# PFC_Stage.net
KiCad netlist of a schematic drawn in Altium Designer
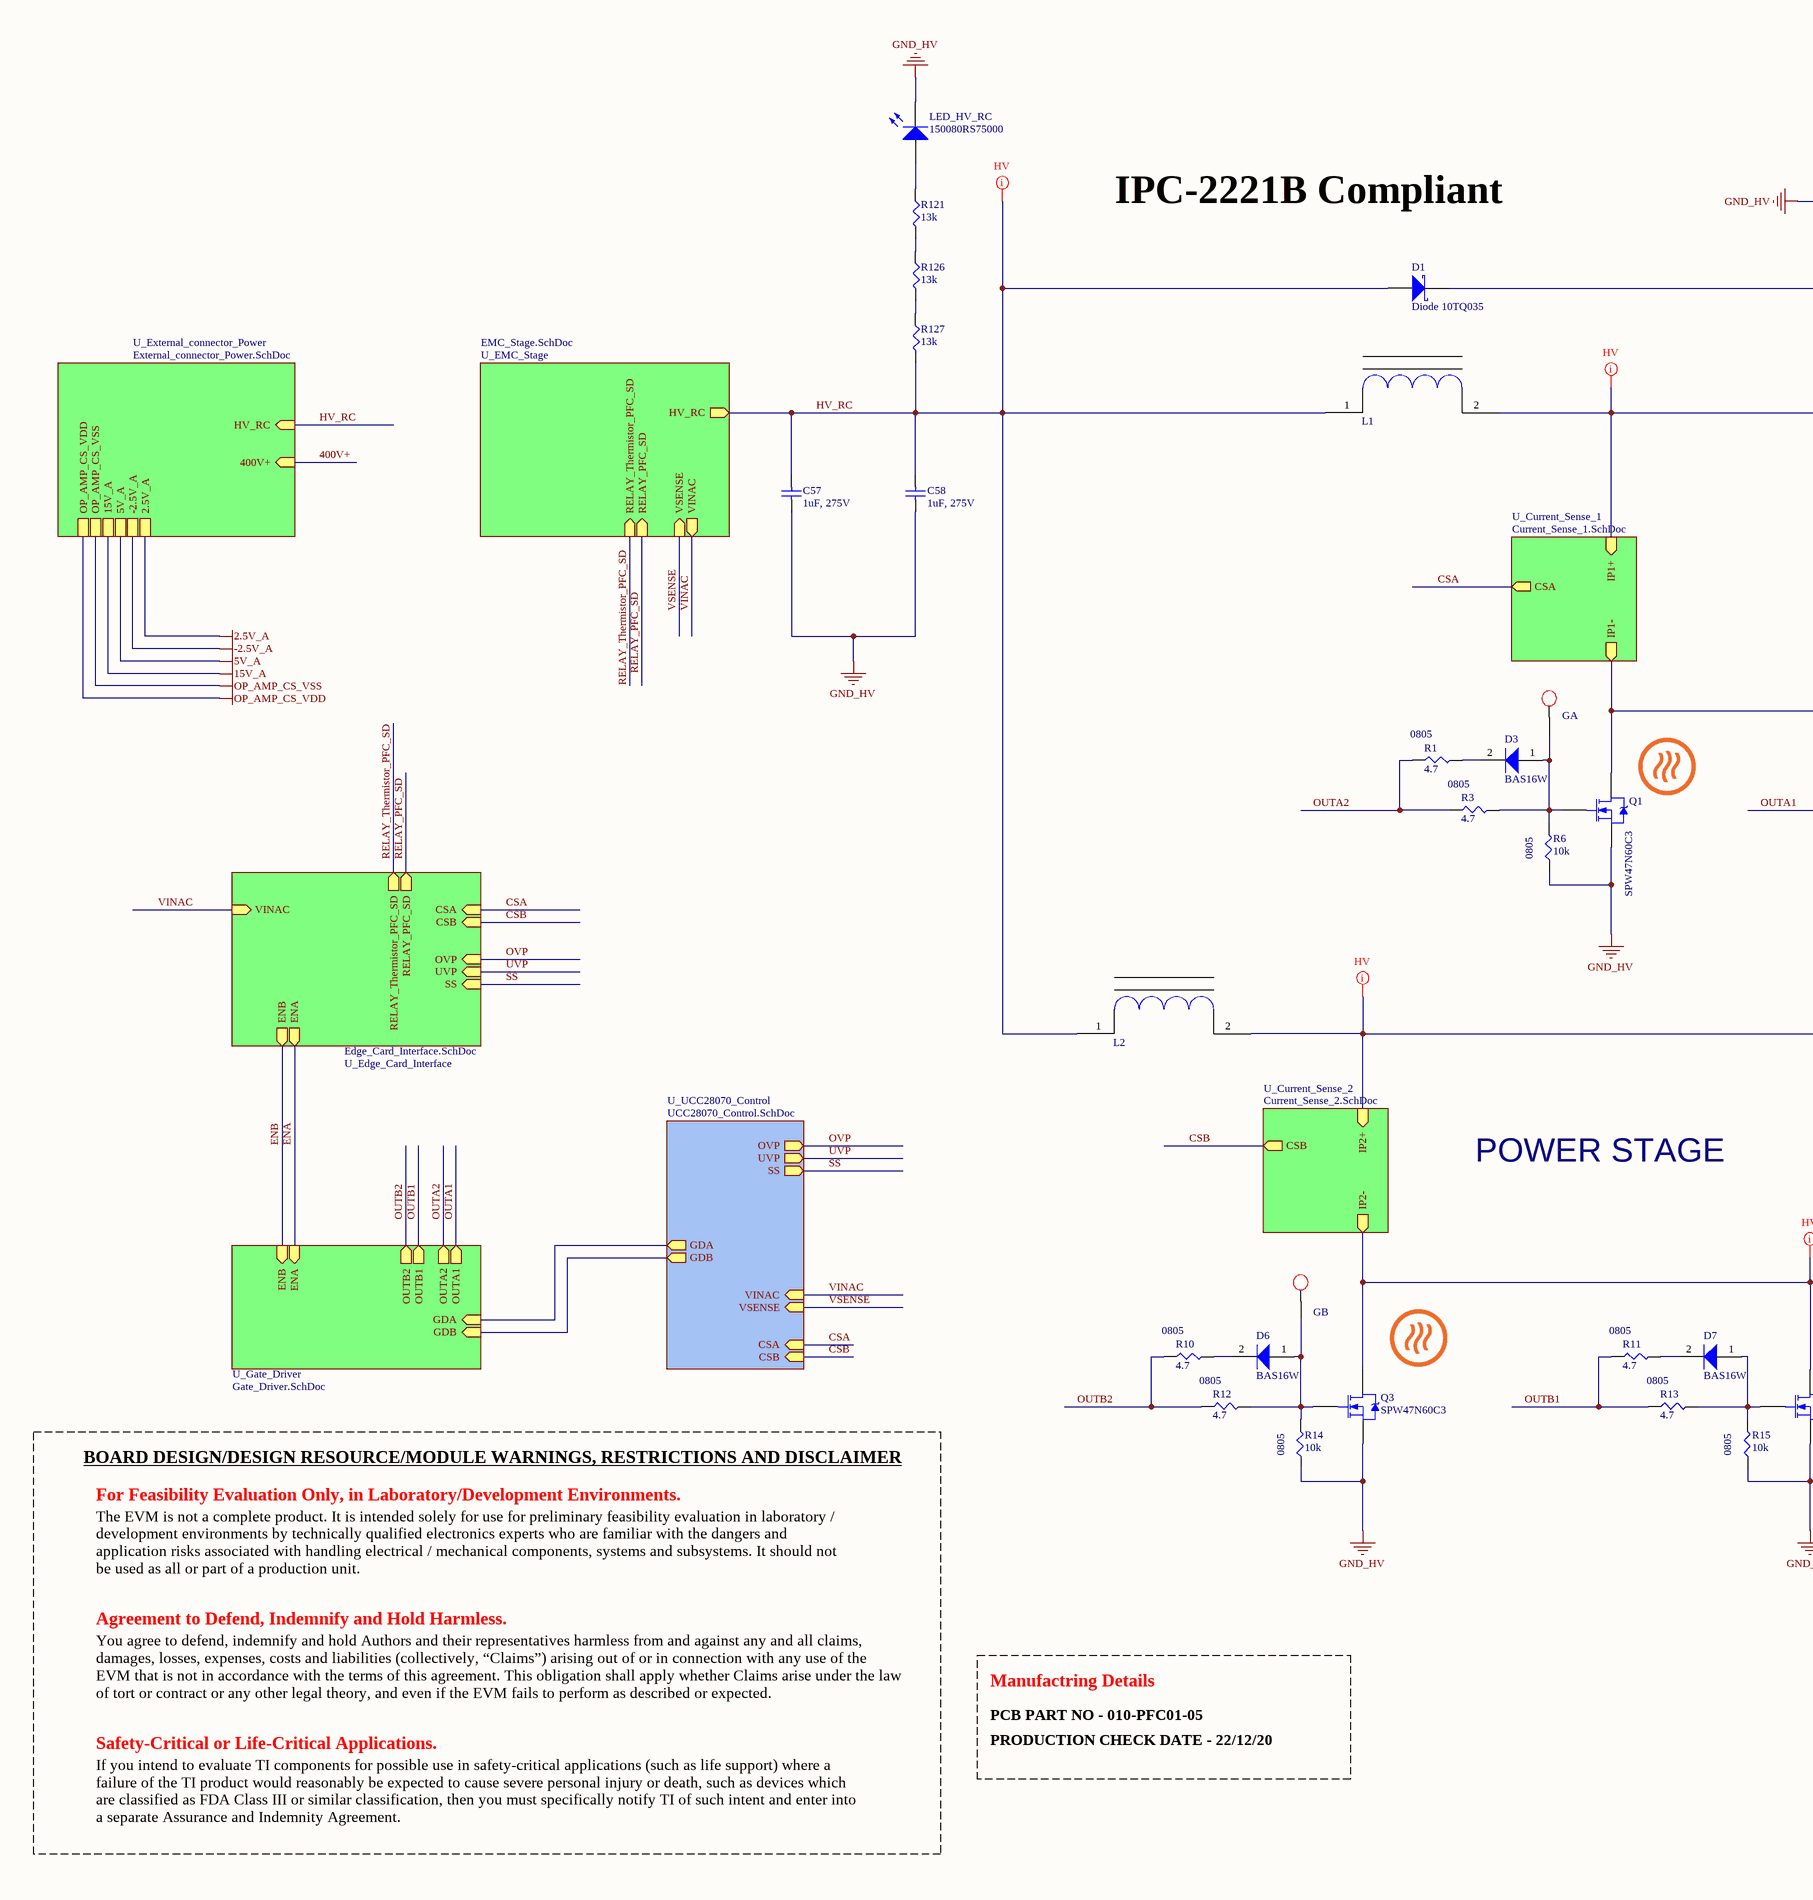
[diagram p0: PFC_Stage.SchDoc, left]
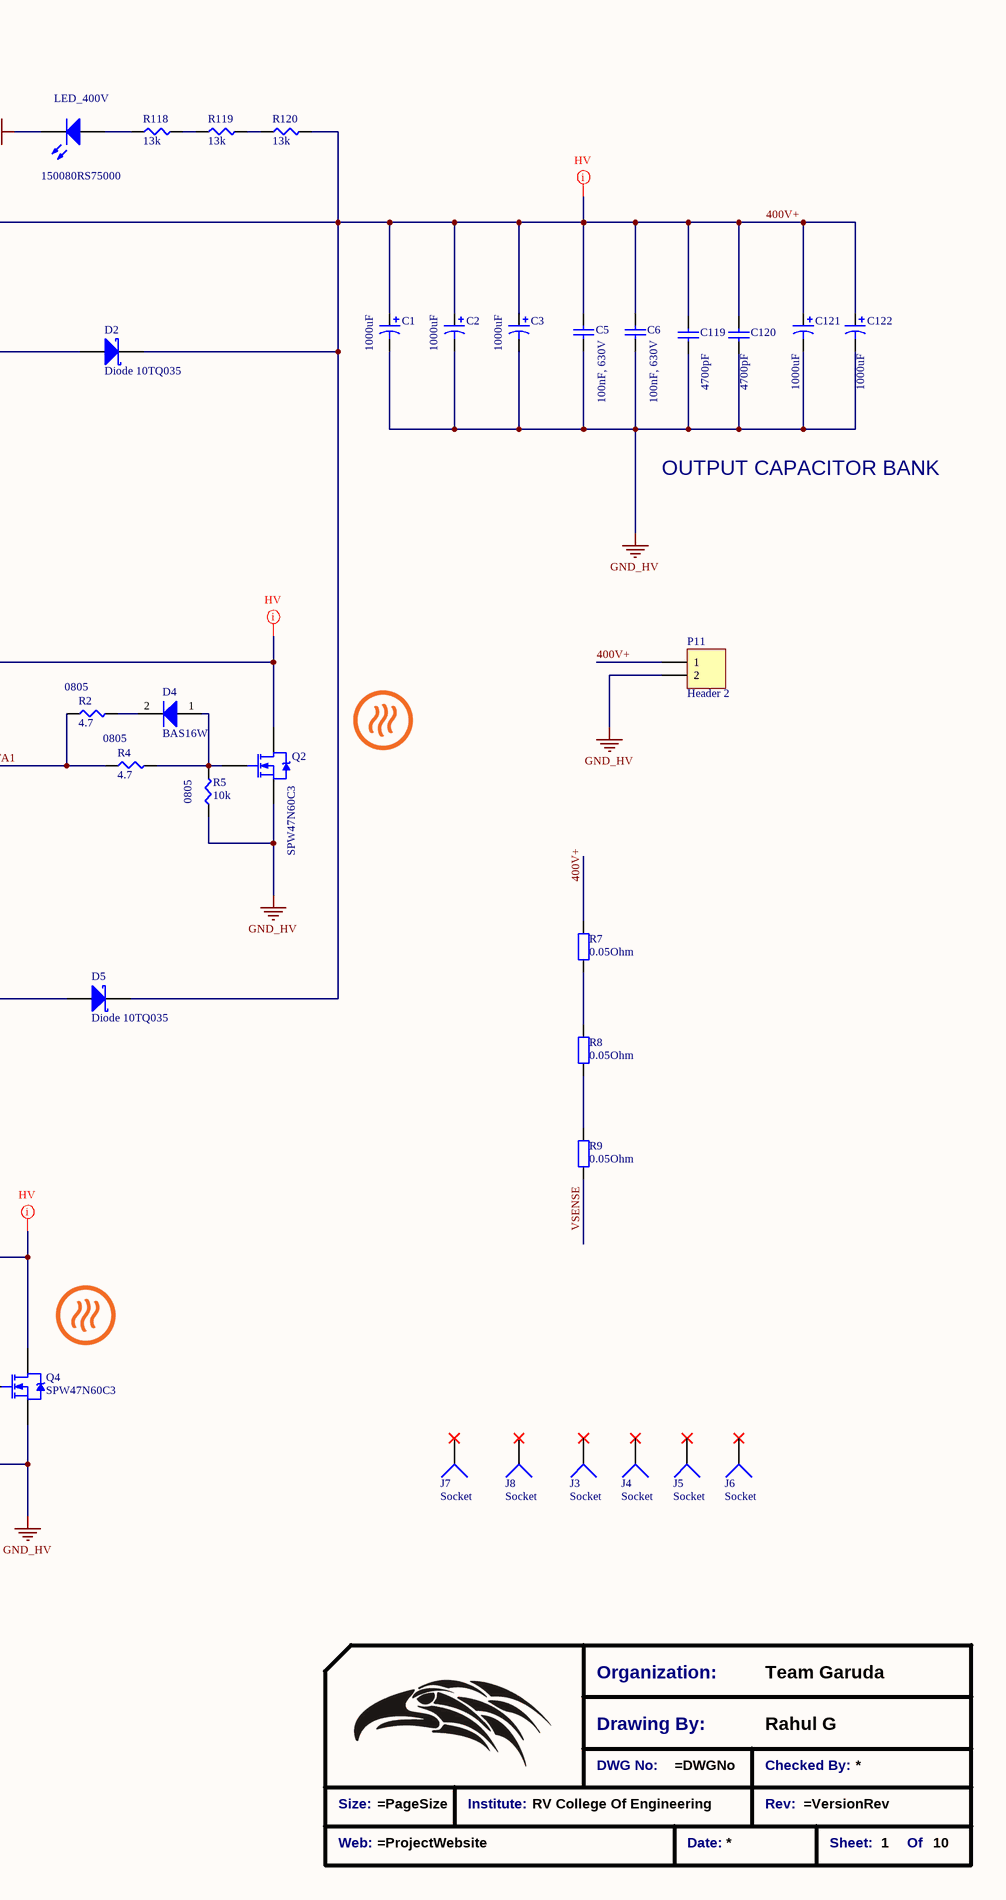
[diagram p1: PFC_Stage.SchDoc, right]

(export (version "E")
  (design (tool "Eeschema 10.0.6"))
  (components
    (comp (ref "*")
      (value "Title_Block")
      (description "Standard Title Block")
      (libsource (lib "PFC_Stage") (part "Title_Block"))
    )
    (comp (ref "C1")
      (value "1000uF")
      (footprint "450V_40mm_10mm")
      (description "Polarized Capacitor (Radial)")
      (fields (field (name "Comment") "40mm") (field (name "PUBLISHER") "Altium Limited"))
      (libsource (lib "Miscellaneous Devices") (part "Cap Pol1"))
    )
    (comp (ref "C2")
      (value "1000uF")
      (footprint "450V_40mm_10mm")
      (description "Polarized Capacitor (Radial)")
      (fields (field (name "Comment") "40mm") (field (name "PUBLISHER") "Altium Limited"))
      (libsource (lib "Miscellaneous Devices") (part "Cap Pol1"))
    )
    (comp (ref "C3")
      (value "1000uF")
      (footprint "450V_40mm_10mm")
      (description "Polarized Capacitor (Radial)")
      (fields (field (name "Comment") "40mm") (field (name "PUBLISHER") "Altium Limited"))
      (libsource (lib "Miscellaneous Devices") (part "Cap Pol1"))
    )
    (comp (ref "C5")
      (value "100nF, 630V")
      (footprint "L18_W6_H12_P15")
      (description "WCAP-FTBE THT Film Capacitors, 100nF, 630VDC")
      (fields (field (name "PART NUMBER") "890303425004CS") (field (name "PUBLISHER") "Wurth Elektronik"))
      (libsource (lib "Altium_WCAP-FTBE_rev19a") (part "890303425004CS"))
    )
    (comp (ref "C6")
      (value "100nF, 630V")
      (footprint "L18_W6_H12_P15")
      (description "WCAP-FTBE THT Film Capacitors, 100nF, 630VDC")
      (fields (field (name "PART NUMBER") "890303425004CS") (field (name "PUBLISHER") "Wurth Elektronik"))
      (libsource (lib "Altium_WCAP-FTBE_rev19a") (part "890303425004CS"))
    )
    (comp (ref "C57")
      (value "1uF, 275V")
      (footprint "L26_W11_H20_P22.5_CS")
      (description "WCAP-FTX2 THT Film Capacitors, 1uF, 275VAC")
      (fields (field (name "PART NUMBER") "890324026027CS") (field (name "PUBLISHER") "Wurth Elektronik"))
      (libsource (lib "Altium_WCAP-FTX2_rev19a") (part "890324026027CS"))
    )
    (comp (ref "C58")
      (value "1uF, 275V")
      (footprint "L26_W11_H20_P22.5_CS")
      (description "WCAP-FTX2 THT Film Capacitors, 1uF, 275VAC")
      (fields (field (name "PART NUMBER") "890324026027CS") (field (name "PUBLISHER") "Wurth Elektronik"))
      (libsource (lib "Altium_WCAP-FTX2_rev19a") (part "890324026027CS"))
    )
    (comp (ref "C119")
      (value "4700pF")
      (footprint "VY1472M61Y5UC63V0")
      (description "Capacitor")
      (fields (field (name "Comment") "VY1472M61Y5UC63V0") (field (name "PUBLISHER") "Altium Limited"))
      (libsource (lib "PFC_Stage") (part "VY1472M61Y5UC63V0"))
    )
    (comp (ref "C120")
      (value "4700pF")
      (footprint "VY1472M61Y5UC63V0")
      (description "Capacitor")
      (fields (field (name "Comment") "VY1472M61Y5UC63V0") (field (name "PUBLISHER") "Altium Limited"))
      (libsource (lib "PFC_Stage") (part "VY1472M61Y5UC63V0"))
    )
    (comp (ref "C121")
      (value "1000uF")
      (footprint "450V_40mm_10mm")
      (description "Polarized Capacitor (Radial)")
      (fields (field (name "Comment") "40mm") (field (name "PUBLISHER") "Altium Limited"))
      (libsource (lib "Miscellaneous Devices") (part "Cap Pol1"))
    )
    (comp (ref "C122")
      (value "1000uF")
      (footprint "450V_40mm_10mm")
      (description "Polarized Capacitor (Radial)")
      (fields (field (name "Comment") "40mm") (field (name "PUBLISHER") "Altium Limited"))
      (libsource (lib "Miscellaneous Devices") (part "Cap Pol1"))
    )
    (comp (ref "D1")
      (value "Diode 10TQ035")
      (footprint "INF-PG-TO247-2-MOD")
      (description "Schottky Rectifier")
      (fields (field (name "PUBLISHER") "Altium Limited"))
      (libsource (lib "Miscellaneous Devices") (part "Diode 10TQ035"))
    )
    (comp (ref "D2")
      (value "Diode 10TQ035")
      (footprint "INF-PG-TO247-2-MOD")
      (description "Schottky Rectifier")
      (fields (field (name "PUBLISHER") "Altium Limited"))
      (libsource (lib "Miscellaneous Devices") (part "Diode 10TQ035"))
    )
    (comp (ref "D3")
      (value "BAS16W")
      (footprint "SODFL250X110-2N")
      (description "Silicon Switching Diode, SOT323, Reel, Green")
      (fields (field (name "MANUFACTURER") "Infineon"))
      (libsource (lib "PFC_Stage") (part "BAS16_SOD"))
    )
    (comp (ref "D4")
      (value "BAS16W")
      (footprint "SODFL250X110-2N")
      (description "Silicon Switching Diode, SOT323, Reel, Green")
      (fields (field (name "MANUFACTURER") "Infineon"))
      (libsource (lib "PFC_Stage") (part "BAS16_SOD"))
    )
    (comp (ref "D5")
      (value "Diode 10TQ035")
      (footprint "INF-PG-TO247-2-MOD")
      (description "Schottky Rectifier")
      (fields (field (name "PUBLISHER") "Altium Limited"))
      (libsource (lib "Miscellaneous Devices") (part "Diode 10TQ035"))
    )
    (comp (ref "D6")
      (value "BAS16W")
      (footprint "SODFL250X110-2N")
      (description "Silicon Switching Diode, SOT323, Reel, Green")
      (fields (field (name "MANUFACTURER") "Infineon"))
      (libsource (lib "PFC_Stage") (part "BAS16_SOD"))
    )
    (comp (ref "D7")
      (value "BAS16W")
      (footprint "SODFL250X110-2N")
      (description "Silicon Switching Diode, SOT323, Reel, Green")
      (fields (field (name "MANUFACTURER") "Infineon"))
      (libsource (lib "PFC_Stage") (part "BAS16_SOD"))
    )
    (comp (ref "GA")
      (value "Test Point")
      (footprint "Test_point_SMD")
      (description "TP")
      (libsource (lib "PFC_Stage") (part "Test Point"))
    )
    (comp (ref "GB")
      (value "Test Point")
      (footprint "Test_point_SMD")
      (description "TP")
      (libsource (lib "PFC_Stage") (part "Test Point"))
    )
    (comp (ref "J3")
      (value "Socket")
      (footprint "Mounting_hole_3mm")
      (fields (field (name "PUBLISHER") "Altium Limited"))
      (libsource (lib "PFC_Stage") (part "Socket"))
    )
    (comp (ref "J4")
      (value "Socket")
      (footprint "Mounting_hole_3mm")
      (fields (field (name "PUBLISHER") "Altium Limited"))
      (libsource (lib "PFC_Stage") (part "Socket"))
    )
    (comp (ref "J5")
      (value "Socket")
      (footprint "Mounting_hole_3mm")
      (fields (field (name "PUBLISHER") "Altium Limited"))
      (libsource (lib "PFC_Stage") (part "Socket"))
    )
    (comp (ref "J6")
      (value "Socket")
      (footprint "Mounting_hole_3mm")
      (fields (field (name "PUBLISHER") "Altium Limited"))
      (libsource (lib "PFC_Stage") (part "Socket"))
    )
    (comp (ref "J7")
      (value "Socket")
      (footprint "Mounting_hole_3mm_no_body")
      (fields (field (name "PUBLISHER") "Altium Limited"))
      (libsource (lib "PFC_Stage") (part "Socket"))
    )
    (comp (ref "J8")
      (value "Socket")
      (footprint "Mounting_hole_3mm_no_body")
      (fields (field (name "PUBLISHER") "Altium Limited"))
      (libsource (lib "PFC_Stage") (part "Socket"))
    )
    (comp (ref "L1")
      (value "Transformer_Inductor")
      (footprint "PFC_Toroid_MPP")
      (libsource (lib "PFC_Stage") (part "Transformer_Inductor"))
    )
    (comp (ref "L2")
      (value "Transformer_Inductor")
      (footprint "PFC_Toroid_MPP")
      (libsource (lib "PFC_Stage") (part "Transformer_Inductor"))
    )
    (comp (ref "LED_400V")
      (value "150080RS75000")
      (footprint "0805_A")
      (description "SMD mono-color Chip LED, WL-SMCW, Red")
      (libsource (lib "WL-SMCW SMD chip LED top view mono-color waterclear") (part "150080RS75000"))
    )
    (comp (ref "LED_HV_RC")
      (value "150080RS75000")
      (footprint "0805_A")
      (description "SMD mono-color Chip LED, WL-SMCW, Red")
      (libsource (lib "WL-SMCW SMD chip LED top view mono-color waterclear") (part "150080RS75000"))
    )
    (comp (ref "P11")
      (value "Header 2")
      (footprint "Barrier_Strip_2")
      (description "Header, 2-Pin")
      (fields (field (name "PUBLISHER") "Altium Limited"))
      (libsource (lib "Miscellaneous Connectors") (part "Header 2"))
    )
    (comp (ref "Q1")
      (value "SPW47N60C3")
      (footprint "INF-PG-TO247-3-44")
      (description "N-Channel Power MOSFET")
      (fields (field (name "PUBLISHER") "Altium Limited"))
      (libsource (lib "Miscellaneous Devices") (part "NMOS-2"))
    )
    (comp (ref "Q2")
      (value "SPW47N60C3")
      (footprint "INF-PG-TO247-3-44")
      (description "N-Channel Power MOSFET")
      (fields (field (name "PUBLISHER") "Altium Limited"))
      (libsource (lib "Miscellaneous Devices") (part "NMOS-2"))
    )
    (comp (ref "Q3")
      (value "SPW47N60C3")
      (footprint "INF-PG-TO247-3-44")
      (description "N-Channel Power MOSFET")
      (fields (field (name "PUBLISHER") "Altium Limited"))
      (libsource (lib "Miscellaneous Devices") (part "NMOS-2"))
    )
    (comp (ref "Q4")
      (value "SPW47N60C3")
      (footprint "INF-PG-TO247-3-44")
      (description "N-Channel Power MOSFET")
      (fields (field (name "PUBLISHER") "Altium Limited"))
      (libsource (lib "Miscellaneous Devices") (part "NMOS-2"))
    )
    (comp (ref "R1")
      (value "4.7")
      (footprint "SMD-0805-RES")
      (description "RES SMD 4.7 OHM 1% 1/3W 0805")
      (fields
        (field (name "PART NUMBER") "ERJ-6BQF4R7V")
        (field (name "DIGI-KEY PART NUMBER") "P15995CT-ND")
        (field (name "SUPPLIER DEVICE PACKAGE") "0805")
      )
      (libsource (lib "Panasonic_ERJ_0805") (part "ERJ-6BQF4R7V"))
    )
    (comp (ref "R2")
      (value "4.7")
      (footprint "SMD-0805-RES")
      (description "RES SMD 4.7 OHM 1% 1/3W 0805")
      (fields
        (field (name "PART NUMBER") "ERJ-6BQF4R7V")
        (field (name "DIGI-KEY PART NUMBER") "P15995CT-ND")
        (field (name "SUPPLIER DEVICE PACKAGE") "0805")
      )
      (libsource (lib "Panasonic_ERJ_0805") (part "ERJ-6BQF4R7V"))
    )
    (comp (ref "R3")
      (value "4.7")
      (footprint "SMD-0805-RES")
      (description "RES SMD 4.7 OHM 1% 1/3W 0805")
      (fields
        (field (name "PART NUMBER") "ERJ-6BQF4R7V")
        (field (name "DIGI-KEY PART NUMBER") "P15995CT-ND")
        (field (name "SUPPLIER DEVICE PACKAGE") "0805")
      )
      (libsource (lib "Panasonic_ERJ_0805") (part "ERJ-6BQF4R7V"))
    )
    (comp (ref "R4")
      (value "4.7")
      (footprint "SMD-0805-RES")
      (description "RES SMD 4.7 OHM 1% 1/3W 0805")
      (fields
        (field (name "PART NUMBER") "ERJ-6BQF4R7V")
        (field (name "DIGI-KEY PART NUMBER") "P15995CT-ND")
        (field (name "SUPPLIER DEVICE PACKAGE") "0805")
      )
      (libsource (lib "Panasonic_ERJ_0805") (part "ERJ-6BQF4R7V"))
    )
    (comp (ref "R5")
      (value "10k")
      (footprint "SMD-0805-RES")
      (description "RES SMD 10K OHM 1% 1/8W 0805")
      (fields
        (field (name "PART NUMBER") "ERJ-6ENF1002V")
        (field (name "DIGI-KEY PART NUMBER") "P10.0KCCT-ND")
        (field (name "SUPPLIER DEVICE PACKAGE") "0805")
      )
      (libsource (lib "Panasonic_ERJ_0805") (part "ERJ-6ENF1002V"))
    )
    (comp (ref "R6")
      (value "10k")
      (footprint "SMD-0805-RES")
      (description "RES SMD 10K OHM 1% 1/8W 0805")
      (fields
        (field (name "PART NUMBER") "ERJ-6ENF1002V")
        (field (name "DIGI-KEY PART NUMBER") "P10.0KCCT-ND")
        (field (name "SUPPLIER DEVICE PACKAGE") "0805")
      )
      (libsource (lib "Panasonic_ERJ_0805") (part "ERJ-6ENF1002V"))
    )
    (comp (ref "R7")
      (value "0.05Ohm")
      (footprint "WRIS-KSKE_1206_H=0.6mm")
      (description "WRIS-KSKE Thick Film Resistors, size 1206, 0.05Ohm, +/-1%, 0.5W")
      (fields (field (name "PART NUMBER") "560050332001") (field (name "PUBLISHER") "Wurth Elektronik"))
      (libsource (lib "Altium_WRIS-KSKE_rev19a") (part "560050332001"))
    )
    (comp (ref "R8")
      (value "0.05Ohm")
      (footprint "WRIS-KSKE_1206_H=0.6mm")
      (description "WRIS-KSKE Thick Film Resistors, size 1206, 0.05Ohm, +/-1%, 0.5W")
      (fields (field (name "PART NUMBER") "560050332001") (field (name "PUBLISHER") "Wurth Elektronik"))
      (libsource (lib "Altium_WRIS-KSKE_rev19a") (part "560050332001"))
    )
    (comp (ref "R9")
      (value "0.05Ohm")
      (footprint "WRIS-KSKE_1206_H=0.6mm")
      (description "WRIS-KSKE Thick Film Resistors, size 1206, 0.05Ohm, +/-1%, 0.5W")
      (fields (field (name "PART NUMBER") "560050332001") (field (name "PUBLISHER") "Wurth Elektronik"))
      (libsource (lib "Altium_WRIS-KSKE_rev19a") (part "560050332001"))
    )
    (comp (ref "R10")
      (value "4.7")
      (footprint "SMD-0805-RES")
      (description "RES SMD 4.7 OHM 1% 1/3W 0805")
      (fields
        (field (name "PART NUMBER") "ERJ-6BQF4R7V")
        (field (name "DIGI-KEY PART NUMBER") "P15995CT-ND")
        (field (name "SUPPLIER DEVICE PACKAGE") "0805")
      )
      (libsource (lib "Panasonic_ERJ_0805") (part "ERJ-6BQF4R7V"))
    )
    (comp (ref "R11")
      (value "4.7")
      (footprint "SMD-0805-RES")
      (description "RES SMD 4.7 OHM 1% 1/3W 0805")
      (fields
        (field (name "PART NUMBER") "ERJ-6BQF4R7V")
        (field (name "DIGI-KEY PART NUMBER") "P15995CT-ND")
        (field (name "SUPPLIER DEVICE PACKAGE") "0805")
      )
      (libsource (lib "Panasonic_ERJ_0805") (part "ERJ-6BQF4R7V"))
    )
    (comp (ref "R12")
      (value "4.7")
      (footprint "SMD-0805-RES")
      (description "RES SMD 4.7 OHM 1% 1/3W 0805")
      (fields
        (field (name "PART NUMBER") "ERJ-6BQF4R7V")
        (field (name "DIGI-KEY PART NUMBER") "P15995CT-ND")
        (field (name "SUPPLIER DEVICE PACKAGE") "0805")
      )
      (libsource (lib "Panasonic_ERJ_0805") (part "ERJ-6BQF4R7V"))
    )
    (comp (ref "R13")
      (value "4.7")
      (footprint "SMD-0805-RES")
      (description "RES SMD 4.7 OHM 1% 1/3W 0805")
      (fields
        (field (name "PART NUMBER") "ERJ-6BQF4R7V")
        (field (name "DIGI-KEY PART NUMBER") "P15995CT-ND")
        (field (name "SUPPLIER DEVICE PACKAGE") "0805")
      )
      (libsource (lib "Panasonic_ERJ_0805") (part "ERJ-6BQF4R7V"))
    )
    (comp (ref "R14")
      (value "10k")
      (footprint "SMD-0805-RES")
      (description "RES SMD 10K OHM 1% 1/8W 0805")
      (fields
        (field (name "PART NUMBER") "ERJ-6ENF1002V")
        (field (name "DIGI-KEY PART NUMBER") "P10.0KCCT-ND")
        (field (name "SUPPLIER DEVICE PACKAGE") "0805")
      )
      (libsource (lib "Panasonic_ERJ_0805") (part "ERJ-6ENF1002V"))
    )
    (comp (ref "R15")
      (value "10k")
      (footprint "SMD-0805-RES")
      (description "RES SMD 10K OHM 1% 1/8W 0805")
      (fields
        (field (name "PART NUMBER") "ERJ-6ENF1002V")
        (field (name "DIGI-KEY PART NUMBER") "P10.0KCCT-ND")
        (field (name "SUPPLIER DEVICE PACKAGE") "0805")
      )
      (libsource (lib "Panasonic_ERJ_0805") (part "ERJ-6ENF1002V"))
    )
    (comp (ref "R118")
      (value "13k")
      (footprint "SMD-2512-RES")
      (description "RES SMD 13K OHM 1% 1W 2512")
      (fields
        (field (name "PART NUMBER") "ERJ-1TNF1302U")
        (field (name "DIGI-KEY PART NUMBER") "PT13.0KAFCT-ND")
      )
      (libsource (lib "Panasonic_ERJ_2512") (part "ERJ-1TNF1302U"))
    )
    (comp (ref "R119")
      (value "13k")
      (footprint "SMD-2512-RES")
      (description "RES SMD 13K OHM 1% 1W 2512")
      (fields
        (field (name "PART NUMBER") "ERJ-1TNF1302U")
        (field (name "DIGI-KEY PART NUMBER") "PT13.0KAFCT-ND")
      )
      (libsource (lib "Panasonic_ERJ_2512") (part "ERJ-1TNF1302U"))
    )
    (comp (ref "R120")
      (value "13k")
      (footprint "SMD-2512-RES")
      (description "RES SMD 13K OHM 1% 1W 2512")
      (fields
        (field (name "PART NUMBER") "ERJ-1TNF1302U")
        (field (name "DIGI-KEY PART NUMBER") "PT13.0KAFCT-ND")
      )
      (libsource (lib "Panasonic_ERJ_2512") (part "ERJ-1TNF1302U"))
    )
    (comp (ref "R121")
      (value "13k")
      (footprint "SMD-2512-RES")
      (description "RES SMD 13K OHM 1% 1W 2512")
      (fields
        (field (name "PART NUMBER") "ERJ-1TNF1302U")
        (field (name "DIGI-KEY PART NUMBER") "PT13.0KAFCT-ND")
      )
      (libsource (lib "Panasonic_ERJ_2512") (part "ERJ-1TNF1302U"))
    )
    (comp (ref "R126")
      (value "13k")
      (footprint "SMD-2512-RES")
      (description "RES SMD 13K OHM 1% 1W 2512")
      (fields
        (field (name "PART NUMBER") "ERJ-1TNF1302U")
        (field (name "DIGI-KEY PART NUMBER") "PT13.0KAFCT-ND")
      )
      (libsource (lib "Panasonic_ERJ_2512") (part "ERJ-1TNF1302U"))
    )
    (comp (ref "R127")
      (value "13k")
      (footprint "SMD-2512-RES")
      (description "RES SMD 13K OHM 1% 1W 2512")
      (fields
        (field (name "PART NUMBER") "ERJ-1TNF1302U")
        (field (name "DIGI-KEY PART NUMBER") "PT13.0KAFCT-ND")
      )
      (libsource (lib "Panasonic_ERJ_2512") (part "ERJ-1TNF1302U"))
    )
  )
  (nets
    (net (code "2") (name "/400V+") (class "Default")
      (node (ref "C1") (pin "1") (pinfunction "1_1") (pintype "passive"))
      (node (ref "C119") (pin "2") (pinfunction "2_2") (pintype "passive"))
      (node (ref "C120") (pin "2") (pinfunction "2_2") (pintype "passive"))
      (node (ref "C121") (pin "1") (pinfunction "1_1") (pintype "passive"))
      (node (ref "C122") (pin "1") (pinfunction "1_1") (pintype "passive"))
      (node (ref "C2") (pin "1") (pinfunction "1_1") (pintype "passive"))
      (node (ref "C3") (pin "1") (pinfunction "1_1") (pintype "passive"))
      (node (ref "C5") (pin "2") (pinfunction "2_2") (pintype "passive"))
      (node (ref "C6") (pin "2") (pinfunction "2_2") (pintype "passive"))
      (node (ref "D1") (pin "1") (pinfunction "K_1") (pintype "passive"))
      (node (ref "D2") (pin "1") (pinfunction "K_1") (pintype "passive"))
      (node (ref "D5") (pin "1") (pinfunction "K_1") (pintype "passive"))
      (node (ref "P11") (pin "1") (pinfunction "1_1") (pintype "passive"))
      (node (ref "R120") (pin "2") (pinfunction "2_2") (pintype "passive"))
      (node (ref "R7") (pin "2") (pinfunction "2_2") (pintype "passive"))
    )
    (net (code "9") (name "/HV_RC") (class "Default")
      (node (ref "C57") (pin "2") (pinfunction "2_2") (pintype "passive"))
      (node (ref "C58") (pin "2") (pinfunction "2_2") (pintype "passive"))
      (node (ref "D1") (pin "3") (pinfunction "A_3") (pintype "passive"))
      (node (ref "L1") (pin "1") (pinfunction "1_1") (pintype "passive"))
      (node (ref "L2") (pin "1") (pinfunction "1_1") (pintype "passive"))
      (node (ref "R127") (pin "2") (pinfunction "2_2") (pintype "passive"))
    )
    (net (code "10") (name "/IP1+") (class "Default")
      (node (ref "D2") (pin "3") (pinfunction "A_3") (pintype "passive"))
      (node (ref "L1") (pin "2") (pinfunction "2_2") (pintype "passive"))
    )
    (net (code "11") (name "/IP1-") (class "Default")
      (node (ref "Q1") (pin "2") (pinfunction "D_2") (pintype "passive"))
      (node (ref "Q2") (pin "2") (pinfunction "D_2") (pintype "passive"))
    )
    (net (code "12") (name "/IP2+") (class "Default")
      (node (ref "D5") (pin "3") (pinfunction "A_3") (pintype "passive"))
      (node (ref "L2") (pin "2") (pinfunction "2_2") (pintype "passive"))
    )
    (net (code "13") (name "/IP2-") (class "Default")
      (node (ref "Q3") (pin "2") (pinfunction "D_2") (pintype "passive"))
      (node (ref "Q4") (pin "2") (pinfunction "D_2") (pintype "passive"))
    )
    (net (code "14") (name "/OUTA1") (class "Default")
      (node (ref "R2") (pin "1") (pinfunction "1_1") (pintype "passive"))
      (node (ref "R4") (pin "1") (pinfunction "1_1") (pintype "passive"))
    )
    (net (code "15") (name "/OUTA2") (class "Default")
      (node (ref "R1") (pin "1") (pinfunction "1_1") (pintype "passive"))
      (node (ref "R3") (pin "1") (pinfunction "1_1") (pintype "passive"))
    )
    (net (code "16") (name "/OUTB1") (class "Default")
      (node (ref "R11") (pin "1") (pinfunction "1_1") (pintype "passive"))
      (node (ref "R13") (pin "1") (pinfunction "1_1") (pintype "passive"))
    )
    (net (code "17") (name "/OUTB2") (class "Default")
      (node (ref "R10") (pin "1") (pinfunction "1_1") (pintype "passive"))
      (node (ref "R12") (pin "1") (pinfunction "1_1") (pintype "passive"))
    )
    (net (code "24") (name "/VSENSE") (class "Default")
      (node (ref "R9") (pin "1") (pinfunction "1_1") (pintype "passive"))
    )
    (net (code "28") (name "GND_HV") (class "Default")
      (node (ref "C1") (pin "2") (pinfunction "2_2") (pintype "passive"))
      (node (ref "C119") (pin "1") (pinfunction "1_1") (pintype "passive"))
      (node (ref "C120") (pin "1") (pinfunction "1_1") (pintype "passive"))
      (node (ref "C121") (pin "2") (pinfunction "2_2") (pintype "passive"))
      (node (ref "C122") (pin "2") (pinfunction "2_2") (pintype "passive"))
      (node (ref "C2") (pin "2") (pinfunction "2_2") (pintype "passive"))
      (node (ref "C3") (pin "2") (pinfunction "2_2") (pintype "passive"))
      (node (ref "C5") (pin "1") (pinfunction "1_1") (pintype "passive"))
      (node (ref "C57") (pin "1") (pinfunction "1_1") (pintype "passive"))
      (node (ref "C58") (pin "1") (pinfunction "1_1") (pintype "passive"))
      (node (ref "C6") (pin "1") (pinfunction "1_1") (pintype "passive"))
      (node (ref "LED_400V") (pin "1") (pinfunction "K_1") (pintype "passive"))
      (node (ref "LED_HV_RC") (pin "1") (pinfunction "K_1") (pintype "passive"))
      (node (ref "P11") (pin "2") (pinfunction "2_2") (pintype "passive"))
      (node (ref "Q1") (pin "3") (pinfunction "S_3") (pintype "passive"))
      (node (ref "Q2") (pin "3") (pinfunction "S_3") (pintype "passive"))
      (node (ref "Q3") (pin "3") (pinfunction "S_3") (pintype "passive"))
      (node (ref "Q4") (pin "3") (pinfunction "S_3") (pintype "passive"))
      (node (ref "R14") (pin "1") (pinfunction "1_1") (pintype "passive"))
      (node (ref "R15") (pin "1") (pinfunction "1_1") (pintype "passive"))
      (node (ref "R5") (pin "1") (pinfunction "1_1") (pintype "passive"))
      (node (ref "R6") (pin "1") (pinfunction "1_1") (pintype "passive"))
    )
    (net (code "29") (name "Net-(D3-A)") (class "Default")
      (node (ref "D3") (pin "1") (pinfunction "A_1") (pintype "passive"))
      (node (ref "GA") (pin "1") (pinfunction "1_1") (pintype "passive"))
      (node (ref "Q1") (pin "1") (pinfunction "G_1") (pintype "passive"))
      (node (ref "R3") (pin "2") (pinfunction "2_2") (pintype "passive"))
      (node (ref "R6") (pin "2") (pinfunction "2_2") (pintype "passive"))
    )
    (net (code "30") (name "Net-(D3-K)") (class "Default")
      (node (ref "D3") (pin "2") (pinfunction "K_2") (pintype "passive"))
      (node (ref "R1") (pin "2") (pinfunction "2_2") (pintype "passive"))
    )
    (net (code "31") (name "Net-(D4-A)") (class "Default")
      (node (ref "D4") (pin "1") (pinfunction "A_1") (pintype "passive"))
      (node (ref "Q2") (pin "1") (pinfunction "G_1") (pintype "passive"))
      (node (ref "R4") (pin "2") (pinfunction "2_2") (pintype "passive"))
      (node (ref "R5") (pin "2") (pinfunction "2_2") (pintype "passive"))
    )
    (net (code "32") (name "Net-(D4-K)") (class "Default")
      (node (ref "D4") (pin "2") (pinfunction "K_2") (pintype "passive"))
      (node (ref "R2") (pin "2") (pinfunction "2_2") (pintype "passive"))
    )
    (net (code "33") (name "Net-(D6-A)") (class "Default")
      (node (ref "D6") (pin "1") (pinfunction "A_1") (pintype "passive"))
      (node (ref "GB") (pin "1") (pinfunction "1_1") (pintype "passive"))
      (node (ref "Q3") (pin "1") (pinfunction "G_1") (pintype "passive"))
      (node (ref "R12") (pin "2") (pinfunction "2_2") (pintype "passive"))
      (node (ref "R14") (pin "2") (pinfunction "2_2") (pintype "passive"))
    )
    (net (code "34") (name "Net-(D6-K)") (class "Default")
      (node (ref "D6") (pin "2") (pinfunction "K_2") (pintype "passive"))
      (node (ref "R10") (pin "2") (pinfunction "2_2") (pintype "passive"))
    )
    (net (code "35") (name "Net-(D7-A)") (class "Default")
      (node (ref "D7") (pin "1") (pinfunction "A_1") (pintype "passive"))
      (node (ref "Q4") (pin "1") (pinfunction "G_1") (pintype "passive"))
      (node (ref "R13") (pin "2") (pinfunction "2_2") (pintype "passive"))
      (node (ref "R15") (pin "2") (pinfunction "2_2") (pintype "passive"))
    )
    (net (code "36") (name "Net-(D7-K)") (class "Default")
      (node (ref "D7") (pin "2") (pinfunction "K_2") (pintype "passive"))
      (node (ref "R11") (pin "2") (pinfunction "2_2") (pintype "passive"))
    )
    (net (code "37") (name "Net-(LED_400V-A)") (class "Default")
      (node (ref "LED_400V") (pin "2") (pinfunction "A_2") (pintype "passive"))
      (node (ref "R118") (pin "1") (pinfunction "1_1") (pintype "passive"))
    )
    (net (code "38") (name "Net-(LED_HV_RC-A)") (class "Default")
      (node (ref "LED_HV_RC") (pin "2") (pinfunction "A_2") (pintype "passive"))
      (node (ref "R121") (pin "1") (pinfunction "1_1") (pintype "passive"))
    )
    (net (code "39") (name "Net-(R7-Pad1)") (class "Default")
      (node (ref "R7") (pin "1") (pinfunction "1_1") (pintype "passive"))
      (node (ref "R8") (pin "2") (pinfunction "2_2") (pintype "passive"))
    )
    (net (code "40") (name "Net-(R8-Pad1)") (class "Default")
      (node (ref "R8") (pin "1") (pinfunction "1_1") (pintype "passive"))
      (node (ref "R9") (pin "2") (pinfunction "2_2") (pintype "passive"))
    )
    (net (code "41") (name "Net-(R118-Pad2)") (class "Default")
      (node (ref "R118") (pin "2") (pinfunction "2_2") (pintype "passive"))
      (node (ref "R119") (pin "1") (pinfunction "1_1") (pintype "passive"))
    )
    (net (code "42") (name "Net-(R119-Pad2)") (class "Default")
      (node (ref "R119") (pin "2") (pinfunction "2_2") (pintype "passive"))
      (node (ref "R120") (pin "1") (pinfunction "1_1") (pintype "passive"))
    )
    (net (code "43") (name "Net-(R121-Pad2)") (class "Default")
      (node (ref "R121") (pin "2") (pinfunction "2_2") (pintype "passive"))
      (node (ref "R126") (pin "1") (pinfunction "1_1") (pintype "passive"))
    )
    (net (code "44") (name "Net-(R126-Pad2)") (class "Default")
      (node (ref "R126") (pin "2") (pinfunction "2_2") (pintype "passive"))
      (node (ref "R127") (pin "1") (pinfunction "1_1") (pintype "passive"))
    )
    (net (code "47") (name "unconnected-(J3-Pad1)") (class "Default")
      (node (ref "J3") (pin "1") (pinfunction "1_1") (pintype "passive+no_connect"))
    )
    (net (code "48") (name "unconnected-(J4-Pad1)") (class "Default")
      (node (ref "J4") (pin "1") (pinfunction "1_1") (pintype "passive+no_connect"))
    )
    (net (code "49") (name "unconnected-(J5-Pad1)") (class "Default")
      (node (ref "J5") (pin "1") (pinfunction "1_1") (pintype "passive+no_connect"))
    )
    (net (code "50") (name "unconnected-(J6-Pad1)") (class "Default")
      (node (ref "J6") (pin "1") (pinfunction "1_1") (pintype "passive+no_connect"))
    )
    (net (code "51") (name "unconnected-(J7-Pad1)") (class "Default")
      (node (ref "J7") (pin "1") (pinfunction "1_1") (pintype "passive+no_connect"))
    )
    (net (code "52") (name "unconnected-(J8-Pad1)") (class "Default")
      (node (ref "J8") (pin "1") (pinfunction "1_1") (pintype "passive+no_connect"))
    )
  )
)
